# CAN_3V3.net
KiCad netlist of a schematic drawn in Altium Designer
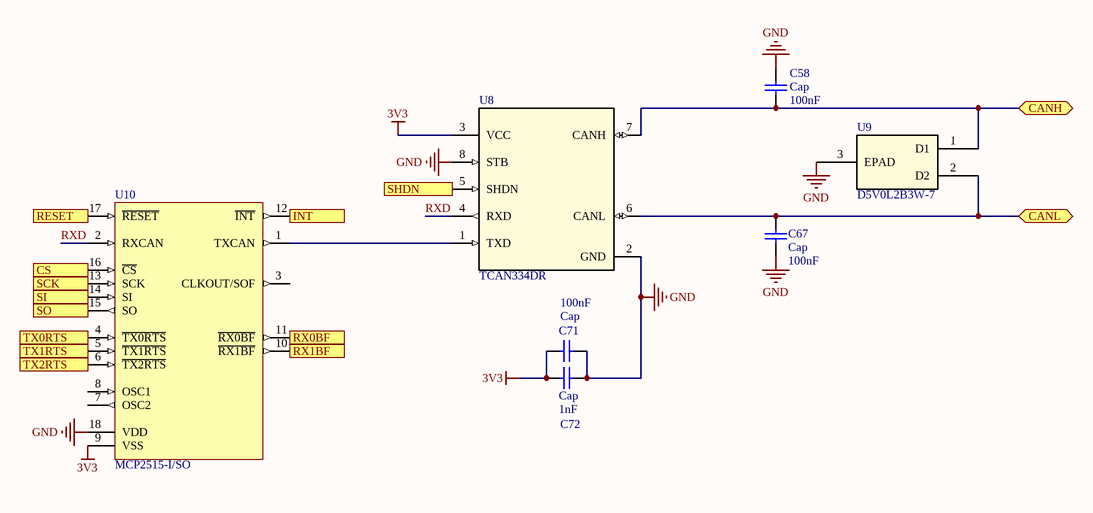
[diagram p0: CAN 3V3.SchDoc]

(export (version "E")
  (design (tool "Eeschema 10.0.6"))
  (components
    (comp (ref "C58")
      (value "Cap")
      (footprint "1608[0603]")
      (description "Capacitor")
      (fields (field (name "ALTIUM_VALUE") "100nF") (field (name "PUBLISHER") "Altium Limited"))
      (libsource (lib "Miscellaneous Devices") (part "Cap"))
    )
    (comp (ref "C67")
      (value "Cap")
      (footprint "1608[0603]")
      (description "Capacitor")
      (fields (field (name "ALTIUM_VALUE") "100nF") (field (name "PUBLISHER") "Altium Limited"))
      (libsource (lib "Miscellaneous Devices") (part "Cap"))
    )
    (comp (ref "C71")
      (value "Cap")
      (footprint "1608[0603]")
      (description "Capacitor")
      (fields (field (name "ALTIUM_VALUE") "100nF") (field (name "PUBLISHER") "Altium Limited"))
      (libsource (lib "Miscellaneous Devices") (part "Cap"))
    )
    (comp (ref "C72")
      (value "Cap")
      (footprint "1608[0603]")
      (description "Capacitor")
      (fields (field (name "ALTIUM_VALUE") "1nF") (field (name "PUBLISHER") "Altium Limited"))
      (libsource (lib "Miscellaneous Devices") (part "Cap"))
    )
    (comp (ref "U8")
      (value "TCAN334DR")
      (footprint "D0008A_N")
      (description "No Description Available")
      (fields
        (field (name "MANUFACTURER") "Texas Instruments")
        (field (name "COPYRIGHT") "Copyright (C) 2018 Accelerated Designs. All rights reserved")
      )
      (libsource (lib "CANTRAN3V3") (part "TCAN334DR"))
    )
    (comp (ref "U9")
      (value "D5V0L2B3W-7")
      (footprint "SOT-323_DIO")
      (description "No Description Available")
      (fields (field (name "COPYRIGHT") "Copyright (C) 2018 Accelerated Designs. All rights reserved"))
      (libsource (lib "D5V0L2B3W-7 library") (part "D5V0L2B3W-7"))
    )
    (comp (ref "U10")
      (value "MCP2515-I/SO")
      (footprint "SOIC-SO18_L")
      (description "Stand-Alone CAN Controller With SPI Interface, 18-Pin SOIC, Industrial Temperature")
      (libsource (lib "Altium Content Vault") (part "COM-CAN-MCP2515-18"))
    )
  )
  (nets
    (net (code "1") (name "/CANH") (class "Default")
      (node (ref "C58") (pin "2") (pinfunction "2_2") (pintype "passive"))
      (node (ref "U8") (pin "7") (pinfunction "CANH_7") (pintype "bidirectional"))
      (node (ref "U9") (pin "1") (pinfunction "D1_1") (pintype "passive"))
    )
    (net (code "2") (name "/CANL") (class "Default")
      (node (ref "C67") (pin "2") (pinfunction "2_2") (pintype "passive"))
      (node (ref "U8") (pin "6") (pinfunction "CANL_6") (pintype "bidirectional"))
      (node (ref "U9") (pin "2") (pinfunction "D2_2") (pintype "passive"))
    )
    (net (code "3") (name "/CS") (class "Default")
      (node (ref "U10") (pin "16") (pinfunction "~{CS}_16") (pintype "input"))
    )
    (net (code "4") (name "/INT") (class "Default")
      (node (ref "U10") (pin "12") (pinfunction "~{INT}_12") (pintype "output"))
    )
    (net (code "5") (name "/RESET") (class "Default")
      (node (ref "U10") (pin "17") (pinfunction "~{RESET}_17") (pintype "input"))
    )
    (net (code "6") (name "/RX0BF") (class "Default")
      (node (ref "U10") (pin "11") (pinfunction "~{RX0BF}_11") (pintype "output"))
    )
    (net (code "7") (name "/RX1BF") (class "Default")
      (node (ref "U10") (pin "10") (pinfunction "~{RX1BF}_10") (pintype "output"))
    )
    (net (code "8") (name "/RXD") (class "Default")
      (node (ref "U10") (pin "2") (pinfunction "RXCAN_2") (pintype "input"))
      (node (ref "U8") (pin "4") (pinfunction "RXD_4") (pintype "output"))
    )
    (net (code "9") (name "/SCK") (class "Default")
      (node (ref "U10") (pin "13") (pinfunction "SCK_13") (pintype "input"))
    )
    (net (code "10") (name "/SHDN") (class "Default")
      (node (ref "U8") (pin "5") (pinfunction "SHDN_5") (pintype "input"))
    )
    (net (code "11") (name "/SI") (class "Default")
      (node (ref "U10") (pin "14") (pinfunction "SI_14") (pintype "input"))
    )
    (net (code "12") (name "/SO") (class "Default")
      (node (ref "U10") (pin "15") (pinfunction "SO_15") (pintype "output"))
    )
    (net (code "13") (name "/TX0RTS") (class "Default")
      (node (ref "U10") (pin "4") (pinfunction "~{TX0RTS}_4") (pintype "input"))
    )
    (net (code "14") (name "/TX1RTS") (class "Default")
      (node (ref "U10") (pin "5") (pinfunction "~{TX1RTS}_5") (pintype "input"))
    )
    (net (code "15") (name "/TX2RTS") (class "Default")
      (node (ref "U10") (pin "6") (pinfunction "~{TX2RTS}_6") (pintype "input"))
    )
    (net (code "16") (name "3V3") (class "Default")
      (node (ref "C71") (pin "1") (pinfunction "1_1") (pintype "passive"))
      (node (ref "C72") (pin "2") (pinfunction "2_2") (pintype "passive"))
      (node (ref "U10") (pin "9") (pinfunction "VSS_9") (pintype "power_in"))
      (node (ref "U8") (pin "3") (pinfunction "VCC_3") (pintype "power_in"))
    )
    (net (code "17") (name "GND") (class "Default")
      (node (ref "C58") (pin "1") (pinfunction "1_1") (pintype "passive"))
      (node (ref "C67") (pin "1") (pinfunction "1_1") (pintype "passive"))
      (node (ref "C71") (pin "2") (pinfunction "2_2") (pintype "passive"))
      (node (ref "C72") (pin "1") (pinfunction "1_1") (pintype "passive"))
      (node (ref "U10") (pin "18") (pinfunction "VDD_18") (pintype "power_in"))
      (node (ref "U8") (pin "2") (pinfunction "GND_2") (pintype "power_in"))
      (node (ref "U8") (pin "8") (pinfunction "STB_8") (pintype "input"))
      (node (ref "U9") (pin "3") (pinfunction "EPAD_3") (pintype "passive"))
    )
    (net (code "18") (name "Net-(U10-TXCAN)") (class "Default")
      (node (ref "U10") (pin "1") (pinfunction "TXCAN_1") (pintype "output"))
      (node (ref "U8") (pin "1") (pinfunction "TXD_1") (pintype "input"))
    )
    (net (code "19") (name "unconnected-(U10-CLKOUT{slash}SOF-Pad3)") (class "Default")
      (node (ref "U10") (pin "3") (pinfunction "CLKOUT/SOF_3") (pintype "output"))
    )
    (net (code "20") (name "unconnected-(U10-OSC1-Pad8)") (class "Default")
      (node (ref "U10") (pin "8") (pinfunction "OSC1_8") (pintype "input"))
    )
    (net (code "21") (name "unconnected-(U10-OSC2-Pad7)") (class "Default")
      (node (ref "U10") (pin "7") (pinfunction "OSC2_7") (pintype "output"))
    )
  )
)
